# RF.net
KiCad netlist of a schematic drawn in Altium Designer
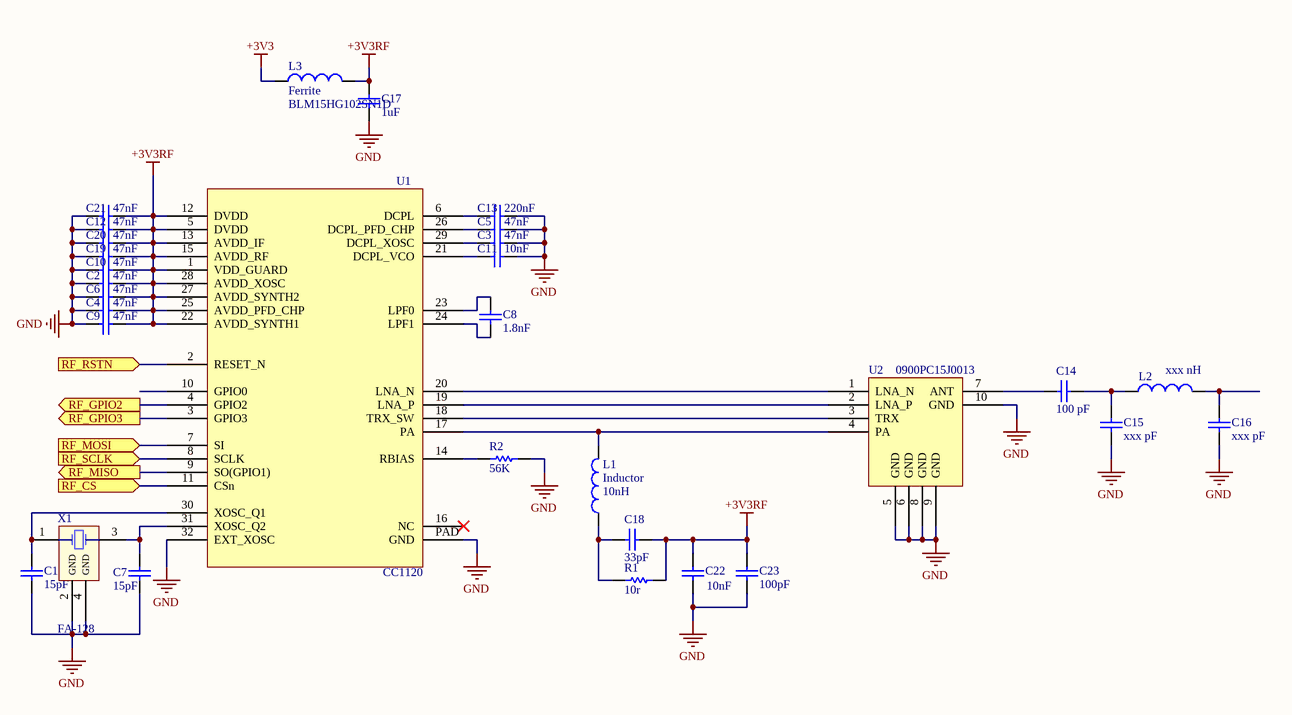
[diagram p0: RF.SchDoc]

(export (version "E")
  (design (tool "Eeschema 10.0.6"))
  (components
    (comp (ref "C1")
      (value "15pF")
      (footprint "0402_ipc")
      (description "Capacitor")
      (fields (field (name "Comment") "Cap") (field (name "PUBLISHER") "Altium Limited"))
      (libsource (lib "LucasLib") (part "Cap"))
    )
    (comp (ref "C2")
      (value "47nF")
      (footprint "0402_ipc")
      (description "Capacitor")
      (fields (field (name "Comment") "Cap") (field (name "PUBLISHER") "Altium Limited"))
      (libsource (lib "LucasLib") (part "Cap"))
    )
    (comp (ref "C3")
      (value "47nF")
      (footprint "0402_ipc")
      (description "Capacitor")
      (fields (field (name "Comment") "Cap") (field (name "PUBLISHER") "Altium Limited"))
      (libsource (lib "LucasLib") (part "Cap"))
    )
    (comp (ref "C4")
      (value "47nF")
      (footprint "0402_ipc")
      (description "Capacitor")
      (fields (field (name "Comment") "Cap") (field (name "PUBLISHER") "Altium Limited"))
      (libsource (lib "LucasLib") (part "Cap"))
    )
    (comp (ref "C5")
      (value "47nF")
      (footprint "0402_ipc")
      (description "Capacitor")
      (fields (field (name "Comment") "Cap") (field (name "PUBLISHER") "Altium Limited"))
      (libsource (lib "LucasLib") (part "Cap"))
    )
    (comp (ref "C6")
      (value "47nF")
      (footprint "0402_ipc")
      (description "Capacitor")
      (fields (field (name "Comment") "Cap") (field (name "PUBLISHER") "Altium Limited"))
      (libsource (lib "LucasLib") (part "Cap"))
    )
    (comp (ref "C7")
      (value "15pF")
      (footprint "0402_ipc")
      (description "Capacitor")
      (fields (field (name "Comment") "Cap") (field (name "PUBLISHER") "Altium Limited"))
      (libsource (lib "LucasLib") (part "Cap"))
    )
    (comp (ref "C8")
      (value "1.8nF")
      (footprint "0402_ipc")
      (description "Capacitor")
      (fields (field (name "Comment") "Cap") (field (name "PUBLISHER") "Altium Limited"))
      (libsource (lib "LucasLib") (part "Cap"))
    )
    (comp (ref "C9")
      (value "47nF")
      (footprint "0402_ipc")
      (description "Capacitor")
      (fields (field (name "Comment") "Cap") (field (name "PUBLISHER") "Altium Limited"))
      (libsource (lib "LucasLib") (part "Cap"))
    )
    (comp (ref "C10")
      (value "47nF")
      (footprint "0402_ipc")
      (description "Capacitor")
      (fields (field (name "Comment") "Cap") (field (name "PUBLISHER") "Altium Limited"))
      (libsource (lib "LucasLib") (part "Cap"))
    )
    (comp (ref "C11")
      (value "10nF")
      (footprint "0402_ipc")
      (description "Capacitor")
      (fields (field (name "Comment") "Cap") (field (name "PUBLISHER") "Altium Limited"))
      (libsource (lib "LucasLib") (part "Cap"))
    )
    (comp (ref "C12")
      (value "47nF")
      (footprint "0402_ipc")
      (description "Capacitor")
      (fields (field (name "Comment") "Cap") (field (name "PUBLISHER") "Altium Limited"))
      (libsource (lib "LucasLib") (part "Cap"))
    )
    (comp (ref "C13")
      (value "220nF")
      (footprint "0402_ipc")
      (description "Capacitor")
      (fields (field (name "Comment") "Cap") (field (name "PUBLISHER") "Altium Limited"))
      (libsource (lib "LucasLib") (part "Cap"))
    )
    (comp (ref "C14")
      (value "100 pF")
      (footprint "0402_ipc")
      (description "Capacitor")
      (fields (field (name "Comment") "Cap") (field (name "PUBLISHER") "Altium Limited"))
      (libsource (lib "LucasLib") (part "Cap"))
    )
    (comp (ref "C15")
      (value "xxx pF")
      (footprint "0402_ipc")
      (description "Capacitor")
      (fields (field (name "Comment") "Cap") (field (name "PUBLISHER") "Altium Limited"))
      (libsource (lib "LucasLib") (part "Cap"))
    )
    (comp (ref "C16")
      (value "xxx pF")
      (footprint "0402_ipc")
      (description "Capacitor")
      (fields (field (name "Comment") "Cap") (field (name "PUBLISHER") "Altium Limited"))
      (libsource (lib "LucasLib") (part "Cap"))
    )
    (comp (ref "C17")
      (value "1uF")
      (footprint "0402_ipc")
      (description "Capacitor")
      (fields (field (name "Comment") "Cap") (field (name "PUBLISHER") "Altium Limited"))
      (libsource (lib "LucasLib") (part "Cap"))
    )
    (comp (ref "C18")
      (value "33pF")
      (footprint "0402_ipc")
      (description "Capacitor")
      (fields (field (name "Comment") "Cap") (field (name "PUBLISHER") "Altium Limited"))
      (libsource (lib "LucasLib") (part "Cap"))
    )
    (comp (ref "C19")
      (value "47nF")
      (footprint "0402_ipc")
      (description "Capacitor")
      (fields (field (name "Comment") "Cap") (field (name "PUBLISHER") "Altium Limited"))
      (libsource (lib "LucasLib") (part "Cap"))
    )
    (comp (ref "C20")
      (value "47nF")
      (footprint "0402_ipc")
      (description "Capacitor")
      (fields (field (name "Comment") "Cap") (field (name "PUBLISHER") "Altium Limited"))
      (libsource (lib "LucasLib") (part "Cap"))
    )
    (comp (ref "C21")
      (value "47nF")
      (footprint "0402_ipc")
      (description "Capacitor")
      (fields (field (name "Comment") "Cap") (field (name "PUBLISHER") "Altium Limited"))
      (libsource (lib "LucasLib") (part "Cap"))
    )
    (comp (ref "C22")
      (value "10nF")
      (footprint "0402_ipc")
      (description "Capacitor")
      (fields (field (name "Comment") "Cap") (field (name "PUBLISHER") "Altium Limited"))
      (libsource (lib "LucasLib") (part "Cap"))
    )
    (comp (ref "C23")
      (value "100pF")
      (footprint "0402_ipc")
      (description "Capacitor")
      (fields (field (name "Comment") "Cap") (field (name "PUBLISHER") "Altium Limited"))
      (libsource (lib "LucasLib") (part "Cap"))
    )
    (comp (ref "L1")
      (value "Inductor")
      (footprint "0402_ipc")
      (fields (field (name "ALTIUM_VALUE") "10nH"))
      (libsource (lib "LucasLib") (part "Inductor"))
    )
    (comp (ref "L2")
      (value "xxx nH")
      (footprint "0402_ipc")
      (description "Inductor")
      (libsource (lib "LucasLib") (part "Inductor"))
    )
    (comp (ref "L3")
      (value "Ferrite")
      (footprint "0402_ipc")
      (description "Inductor")
      (fields (field (name "ALTIUM_VALUE") "BLM15HG102SN1D"))
      (libsource (lib "LucasLib") (part "Inductor"))
    )
    (comp (ref "R1")
      (value "10r")
      (footprint "0402_ipc")
      (description "Resistor")
      (fields (field (name "Comment") "Res"))
      (libsource (lib "LucasLib") (part "Res"))
    )
    (comp (ref "R2")
      (value "56K")
      (footprint "0402_ipc")
      (description "Resistor")
      (fields (field (name "Comment") "Res"))
      (libsource (lib "LucasLib") (part "Res"))
    )
    (comp (ref "U1")
      (value "CC1120")
      (footprint "CC1120_VQFN32")
      (libsource (lib "LucasLib") (part "CC1120"))
    )
    (comp (ref "U2")
      (value "0900PC15J0013")
      (footprint "0900PC15J0013")
      (libsource (lib "LucasLib") (part "0900PC15J0013"))
    )
    (comp (ref "X1")
      (value "FA-128")
      (footprint "FA-128")
      (description "Quartz 32 MHz")
      (libsource (lib "LucasLib") (part "FA-128"))
    )
  )
  (nets
    (net (code "1") (name "+3V3") (class "Default")
      (node (ref "L3") (pin "1") (pinfunction "1_1") (pintype "passive"))
    )
    (net (code "2") (name "+3V3RF") (class "Default")
      (node (ref "C10") (pin "1") (pinfunction "1_1") (pintype "passive"))
      (node (ref "C12") (pin "1") (pinfunction "1_1") (pintype "passive"))
      (node (ref "C17") (pin "2") (pinfunction "2_2") (pintype "passive"))
      (node (ref "C18") (pin "1") (pinfunction "1_1") (pintype "passive"))
      (node (ref "C19") (pin "1") (pinfunction "1_1") (pintype "passive"))
      (node (ref "C2") (pin "1") (pinfunction "1_1") (pintype "passive"))
      (node (ref "C20") (pin "1") (pinfunction "1_1") (pintype "passive"))
      (node (ref "C21") (pin "1") (pinfunction "1_1") (pintype "passive"))
      (node (ref "C22") (pin "2") (pinfunction "2_2") (pintype "passive"))
      (node (ref "C23") (pin "2") (pinfunction "2_2") (pintype "passive"))
      (node (ref "C4") (pin "1") (pinfunction "1_1") (pintype "passive"))
      (node (ref "C6") (pin "1") (pinfunction "1_1") (pintype "passive"))
      (node (ref "C9") (pin "1") (pinfunction "1_1") (pintype "passive"))
      (node (ref "L3") (pin "2") (pinfunction "2_2") (pintype "passive"))
      (node (ref "R1") (pin "2") (pinfunction "2_2") (pintype "passive"))
      (node (ref "U1") (pin "1") (pinfunction "VDD_GUARD_1") (pintype "passive"))
      (node (ref "U1") (pin "12") (pinfunction "DVDD_12") (pintype "passive"))
      (node (ref "U1") (pin "13") (pinfunction "AVDD_IF_13") (pintype "passive"))
      (node (ref "U1") (pin "15") (pinfunction "AVDD_RF_15") (pintype "passive"))
      (node (ref "U1") (pin "22") (pinfunction "AVDD_SYNTH1_22") (pintype "passive"))
      (node (ref "U1") (pin "25") (pinfunction "AVDD_PFD_CHP_25") (pintype "passive"))
      (node (ref "U1") (pin "27") (pinfunction "AVDD_SYNTH2_27") (pintype "passive"))
      (node (ref "U1") (pin "28") (pinfunction "AVDD_XOSC_28") (pintype "passive"))
      (node (ref "U1") (pin "5") (pinfunction "DVDD_5") (pintype "passive"))
    )
    (net (code "3") (name "/RF_CS") (class "Default")
      (node (ref "U1") (pin "11") (pinfunction "CSn_11") (pintype "passive"))
    )
    (net (code "4") (name "/RF_GPIO2") (class "Default")
      (node (ref "U1") (pin "4") (pinfunction "GPIO2_4") (pintype "passive"))
    )
    (net (code "5") (name "/RF_GPIO3") (class "Default")
      (node (ref "U1") (pin "3") (pinfunction "GPIO3_3") (pintype "passive"))
    )
    (net (code "6") (name "/RF_MISO") (class "Default")
      (node (ref "U1") (pin "9") (pinfunction "SO(GPIO1)_9") (pintype "passive"))
    )
    (net (code "7") (name "/RF_MOSI") (class "Default")
      (node (ref "U1") (pin "7") (pinfunction "SI_7") (pintype "passive"))
    )
    (net (code "8") (name "/RF_RSTN") (class "Default")
      (node (ref "U1") (pin "2") (pinfunction "RESET_N_2") (pintype "passive"))
    )
    (net (code "9") (name "/RF_SCLK") (class "Default")
      (node (ref "U1") (pin "8") (pinfunction "SCLK_8") (pintype "passive"))
    )
    (net (code "10") (name "GND") (class "Default")
      (node (ref "C1") (pin "1") (pinfunction "1_1") (pintype "passive"))
      (node (ref "C10") (pin "2") (pinfunction "2_2") (pintype "passive"))
      (node (ref "C11") (pin "1") (pinfunction "1_1") (pintype "passive"))
      (node (ref "C12") (pin "2") (pinfunction "2_2") (pintype "passive"))
      (node (ref "C13") (pin "1") (pinfunction "1_1") (pintype "passive"))
      (node (ref "C15") (pin "1") (pinfunction "1_1") (pintype "passive"))
      (node (ref "C16") (pin "1") (pinfunction "1_1") (pintype "passive"))
      (node (ref "C17") (pin "1") (pinfunction "1_1") (pintype "passive"))
      (node (ref "C19") (pin "2") (pinfunction "2_2") (pintype "passive"))
      (node (ref "C2") (pin "2") (pinfunction "2_2") (pintype "passive"))
      (node (ref "C20") (pin "2") (pinfunction "2_2") (pintype "passive"))
      (node (ref "C21") (pin "2") (pinfunction "2_2") (pintype "passive"))
      (node (ref "C22") (pin "1") (pinfunction "1_1") (pintype "passive"))
      (node (ref "C23") (pin "1") (pinfunction "1_1") (pintype "passive"))
      (node (ref "C3") (pin "1") (pinfunction "1_1") (pintype "passive"))
      (node (ref "C4") (pin "2") (pinfunction "2_2") (pintype "passive"))
      (node (ref "C5") (pin "1") (pinfunction "1_1") (pintype "passive"))
      (node (ref "C6") (pin "2") (pinfunction "2_2") (pintype "passive"))
      (node (ref "C7") (pin "1") (pinfunction "1_1") (pintype "passive"))
      (node (ref "C9") (pin "2") (pinfunction "2_2") (pintype "passive"))
      (node (ref "R2") (pin "1") (pinfunction "1_1") (pintype "passive"))
      (node (ref "U1") (pin "32") (pinfunction "EXT_XOSC_32") (pintype "passive"))
      (node (ref "U1") (pin "PAD") (pinfunction "GND_PAD") (pintype "passive"))
      (node (ref "U2") (pin "10") (pinfunction "GND_10") (pintype "passive"))
      (node (ref "U2") (pin "5") (pinfunction "GND_5") (pintype "passive"))
      (node (ref "U2") (pin "6") (pinfunction "GND_6") (pintype "passive"))
      (node (ref "U2") (pin "8") (pinfunction "GND_8") (pintype "passive"))
      (node (ref "U2") (pin "9") (pinfunction "GND_9") (pintype "passive"))
      (node (ref "X1") (pin "2") (pinfunction "GND_2") (pintype "passive"))
      (node (ref "X1") (pin "4") (pinfunction "GND_4") (pintype "passive"))
    )
    (net (code "11") (name "Net-(C14-Pad1)") (class "Default")
      (node (ref "C14") (pin "1") (pinfunction "1_1") (pintype "passive"))
      (node (ref "C15") (pin "2") (pinfunction "2_2") (pintype "passive"))
      (node (ref "L2") (pin "1") (pinfunction "1_1") (pintype "passive"))
    )
    (net (code "12") (name "Net-(C16-Pad2)") (class "Default")
      (node (ref "C16") (pin "2") (pinfunction "2_2") (pintype "passive"))
      (node (ref "L2") (pin "2") (pinfunction "2_2") (pintype "passive"))
    )
    (net (code "13") (name "Net-(C18-Pad2)") (class "Default")
      (node (ref "C18") (pin "2") (pinfunction "2_2") (pintype "passive"))
      (node (ref "L1") (pin "1") (pinfunction "1_1") (pintype "passive"))
      (node (ref "R1") (pin "1") (pinfunction "1_1") (pintype "passive"))
    )
    (net (code "14") (name "Net-(U1-DCPL)") (class "Default")
      (node (ref "C13") (pin "2") (pinfunction "2_2") (pintype "passive"))
      (node (ref "U1") (pin "6") (pinfunction "DCPL_6") (pintype "passive"))
    )
    (net (code "15") (name "Net-(U1-DCPL_PFD_CHP)") (class "Default")
      (node (ref "C5") (pin "2") (pinfunction "2_2") (pintype "passive"))
      (node (ref "U1") (pin "26") (pinfunction "DCPL_PFD_CHP_26") (pintype "passive"))
    )
    (net (code "16") (name "Net-(U1-DCPL_VCO)") (class "Default")
      (node (ref "C11") (pin "2") (pinfunction "2_2") (pintype "passive"))
      (node (ref "U1") (pin "21") (pinfunction "DCPL_VCO_21") (pintype "passive"))
    )
    (net (code "17") (name "Net-(U1-DCPL_XOSC)") (class "Default")
      (node (ref "C3") (pin "2") (pinfunction "2_2") (pintype "passive"))
      (node (ref "U1") (pin "29") (pinfunction "DCPL_XOSC_29") (pintype "passive"))
    )
    (net (code "18") (name "Net-(U1-LNA_N)") (class "Default")
      (node (ref "U1") (pin "20") (pinfunction "LNA_N_20") (pintype "passive"))
      (node (ref "U2") (pin "1") (pinfunction "LNA_N_1") (pintype "passive"))
    )
    (net (code "19") (name "Net-(U1-LNA_P)") (class "Default")
      (node (ref "U1") (pin "19") (pinfunction "LNA_P_19") (pintype "passive"))
      (node (ref "U2") (pin "2") (pinfunction "LNA_P_2") (pintype "passive"))
    )
    (net (code "20") (name "Net-(U1-LPF0)") (class "Default")
      (node (ref "C8") (pin "2") (pinfunction "2_2") (pintype "passive"))
      (node (ref "U1") (pin "23") (pinfunction "LPF0_23") (pintype "passive"))
    )
    (net (code "21") (name "Net-(U1-LPF1)") (class "Default")
      (node (ref "C8") (pin "1") (pinfunction "1_1") (pintype "passive"))
      (node (ref "U1") (pin "24") (pinfunction "LPF1_24") (pintype "passive"))
    )
    (net (code "22") (name "Net-(U1-PA)") (class "Default")
      (node (ref "L1") (pin "2") (pinfunction "2_2") (pintype "passive"))
      (node (ref "U1") (pin "17") (pinfunction "PA_17") (pintype "passive"))
      (node (ref "U2") (pin "4") (pinfunction "PA_4") (pintype "passive"))
    )
    (net (code "23") (name "Net-(U1-RBIAS)") (class "Default")
      (node (ref "R2") (pin "2") (pinfunction "2_2") (pintype "passive"))
      (node (ref "U1") (pin "14") (pinfunction "RBIAS_14") (pintype "passive"))
    )
    (net (code "24") (name "Net-(U1-TRX_SW)") (class "Default")
      (node (ref "U1") (pin "18") (pinfunction "TRX_SW_18") (pintype "passive"))
      (node (ref "U2") (pin "3") (pinfunction "TRX_3") (pintype "passive"))
    )
    (net (code "25") (name "Net-(U1-XOSC_Q1)") (class "Default")
      (node (ref "C1") (pin "2") (pinfunction "2_2") (pintype "passive"))
      (node (ref "U1") (pin "30") (pinfunction "XOSC_Q1_30") (pintype "passive"))
      (node (ref "X1") (pin "1") (pinfunction "OSC1_1") (pintype "passive"))
    )
    (net (code "26") (name "Net-(U1-XOSC_Q2)") (class "Default")
      (node (ref "C7") (pin "2") (pinfunction "2_2") (pintype "passive"))
      (node (ref "U1") (pin "31") (pinfunction "XOSC_Q2_31") (pintype "passive"))
      (node (ref "X1") (pin "3") (pinfunction "OSC2_3") (pintype "passive"))
    )
    (net (code "27") (name "Net-(U2-ANT)") (class "Default")
      (node (ref "C14") (pin "2") (pinfunction "2_2") (pintype "passive"))
      (node (ref "U2") (pin "7") (pinfunction "ANT_7") (pintype "passive"))
    )
    (net (code "28") (name "unconnected-(U1-GPIO0-Pad10)") (class "Default")
      (node (ref "U1") (pin "10") (pinfunction "GPIO0_10") (pintype "passive"))
    )
    (net (code "29") (name "unconnected-(U1-NC-Pad16)") (class "Default")
      (node (ref "U1") (pin "16") (pinfunction "NC_16") (pintype "passive+no_connect"))
    )
  )
)
